# LT8316.net
KiCad netlist of a schematic drawn in Altium Designer
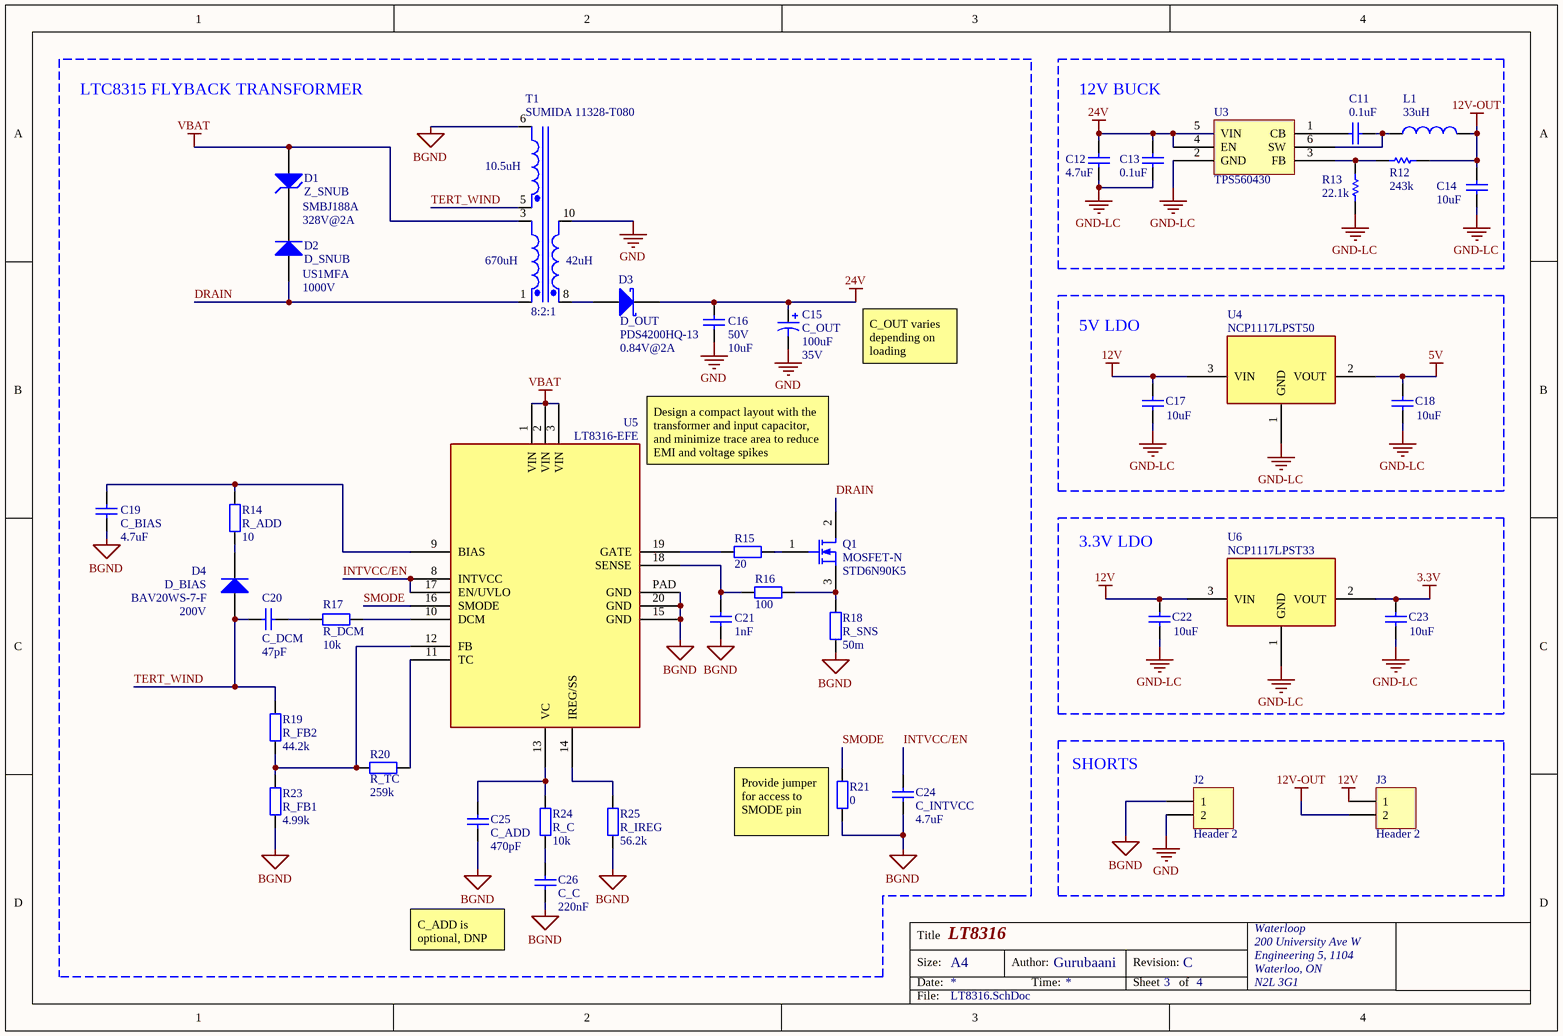
[diagram p0: LT8316.SchDoc]

(export (version "E")
  (design (tool "Eeschema 10.0.6"))
  (components
    (comp (ref "C11")
      (value "0.1uF")
      (footprint "Miscellaneous Devices:C0805")
      (description "Capacitor")
      (fields (field (name "Comment") "C_OUT") (field (name "PUBLISHER") "Altium Limited"))
      (libsource (lib "Miscellaneous Devices") (part "Cap"))
    )
    (comp (ref "C12")
      (value "4.7uF")
      (footprint "Miscellaneous Devices:C0805")
      (description "Capacitor")
      (fields (field (name "Comment") "C_OUT") (field (name "PUBLISHER") "Altium Limited"))
      (libsource (lib "Miscellaneous Devices") (part "Cap"))
    )
    (comp (ref "C13")
      (value "0.1uF")
      (footprint "Miscellaneous Devices:C0805")
      (description "Capacitor")
      (fields (field (name "Comment") "C_OUT") (field (name "PUBLISHER") "Altium Limited"))
      (libsource (lib "Miscellaneous Devices") (part "Cap"))
    )
    (comp (ref "C14")
      (value "10uF")
      (footprint "Miscellaneous Devices:C0805")
      (description "Capacitor")
      (fields (field (name "Comment") "C_OUT") (field (name "PUBLISHER") "Altium Limited"))
      (libsource (lib "Miscellaneous Devices") (part "Cap"))
    )
    (comp (ref "C15")
      (value "C_OUT")
      (footprint "RB7.6-15")
      (description "Polarized Capacitor (Radial)")
      (fields
        (field (name "ALTIUM_VALUE") "100uF")
        (field (name "VOLTAGE") "35V")
        (field (name "PUBLISHER") "Altium Limited")
      )
      (libsource (lib "Miscellaneous Devices") (part "Cap Pol1"))
    )
    (comp (ref "C16")
      (value "10uF")
      (footprint "Miscellaneous Devices:C0805")
      (description "Capacitor")
      (fields
        (field (name "VOLTAGE") "50V")
        (field (name "Comment") "C_OUT")
        (field (name "PUBLISHER") "Altium Limited")
      )
      (libsource (lib "Miscellaneous Devices") (part "Cap"))
    )
    (comp (ref "C17")
      (value "10uF")
      (footprint "Miscellaneous Devices:C0805")
      (description "Capacitor")
      (fields (field (name "Comment") "C_OUT") (field (name "PUBLISHER") "Altium Limited"))
      (libsource (lib "Miscellaneous Devices") (part "Cap"))
    )
    (comp (ref "C18")
      (value "10uF")
      (footprint "Miscellaneous Devices:C0805")
      (description "Capacitor")
      (fields (field (name "Comment") "C_OUT") (field (name "PUBLISHER") "Altium Limited"))
      (libsource (lib "Miscellaneous Devices") (part "Cap"))
    )
    (comp (ref "C19")
      (value "C_BIAS")
      (footprint "Miscellaneous Devices:C0805")
      (description "Capacitor")
      (fields (field (name "ALTIUM_VALUE") "4.7uF") (field (name "PUBLISHER") "Altium Limited"))
      (libsource (lib "Miscellaneous Devices") (part "Cap"))
    )
    (comp (ref "C20")
      (value "C_DCM")
      (footprint "Miscellaneous Devices:C0805")
      (description "Capacitor")
      (fields (field (name "ALTIUM_VALUE") "47pF") (field (name "PUBLISHER") "Altium Limited"))
      (libsource (lib "Miscellaneous Devices") (part "Cap"))
    )
    (comp (ref "C21")
      (value "1nF")
      (footprint "Miscellaneous Devices:C0805")
      (description "Capacitor")
      (fields (field (name "Comment") "C_OUT") (field (name "PUBLISHER") "Altium Limited"))
      (libsource (lib "Miscellaneous Devices") (part "Cap"))
    )
    (comp (ref "C22")
      (value "10uF")
      (footprint "Miscellaneous Devices:C0805")
      (description "Capacitor")
      (fields (field (name "Comment") "C_OUT") (field (name "PUBLISHER") "Altium Limited"))
      (libsource (lib "Miscellaneous Devices") (part "Cap"))
    )
    (comp (ref "C23")
      (value "10uF")
      (footprint "Miscellaneous Devices:C0805")
      (description "Capacitor")
      (fields (field (name "Comment") "C_OUT") (field (name "PUBLISHER") "Altium Limited"))
      (libsource (lib "Miscellaneous Devices") (part "Cap"))
    )
    (comp (ref "C24")
      (value "C_INTVCC")
      (footprint "Miscellaneous Devices:C0805")
      (description "Capacitor")
      (fields (field (name "ALTIUM_VALUE") "4.7uF") (field (name "PUBLISHER") "Altium Limited"))
      (libsource (lib "Miscellaneous Devices") (part "Cap"))
    )
    (comp (ref "C25")
      (value "C_ADD")
      (footprint "Miscellaneous Devices:C0805")
      (description "Capacitor")
      (fields (field (name "ALTIUM_VALUE") "470pF") (field (name "PUBLISHER") "Altium Limited"))
      (libsource (lib "Miscellaneous Devices") (part "Cap"))
    )
    (comp (ref "C26")
      (value "C_C")
      (footprint "Miscellaneous Devices:C0805")
      (description "Capacitor")
      (fields (field (name "ALTIUM_VALUE") "220nF") (field (name "PUBLISHER") "Altium Limited"))
      (libsource (lib "Miscellaneous Devices") (part "Cap"))
    )
    (comp (ref "D1")
      (value "Z_SNUB")
      (footprint "DO-214AA, SMB")
      (description "Zener Diode")
      (fields (field (name "REVERSE VOLTAGE") "328V@2A") (field (name "PARTNUMBER") "SMBJ188A"))
      (libsource (lib "Miscellaneous Devices") (part "D Zener"))
    )
    (comp (ref "D2")
      (value "D_SNUB")
      (footprint "SOD-123FL")
      (description "Default Diode")
      (fields (field (name "REVERSE VOLTAGE") "1000V") (field (name "PARTNUMBER") "US1MFA"))
      (libsource (lib "Miscellaneous Devices") (part "Diode"))
    )
    (comp (ref "D3")
      (value "D_OUT")
      (footprint "POWERDI5 (DPAK184P650X115-3N)")
      (description "Schottky Diode")
      (fields (field (name "FORWARD VOLTAGE") "0.84V@2A") (field (name "PARTNUMBER") "PDS4200HQ-13"))
      (libsource (lib "Miscellaneous Devices") (part "D Schottky"))
    )
    (comp (ref "D4")
      (value "D_BIAS")
      (footprint "SOD323")
      (description "Default Diode")
      (fields (field (name "REVERSE VOLTAGE") "200V") (field (name "PARTNUMBER") "BAV20WS-7-F"))
      (libsource (lib "Miscellaneous Devices") (part "Diode"))
    )
    (comp (ref "J2")
      (value "Header 2")
      (footprint "HDR1X2")
      (description "Header, 2-Pin")
      (fields (field (name "PUBLISHER") "Altium Limited"))
      (libsource (lib "Miscellaneous Connectors") (part "Header 2"))
    )
    (comp (ref "J3")
      (value "Header 2")
      (footprint "HDR1X2")
      (description "Header, 2-Pin")
      (fields (field (name "PUBLISHER") "Altium Limited"))
      (libsource (lib "Miscellaneous Connectors") (part "Header 2"))
    )
    (comp (ref "L1")
      (value "33uH")
      (footprint "INDC4532")
      (description "Inductor")
      (fields (field (name "PUBLISHER") "Altium Limited"))
      (libsource (lib "Miscellaneous Devices") (part "Inductor"))
    )
    (comp (ref "Q1")
      (value "MOSFET-N")
      (footprint "DPAK (228P972X240-3N)")
      (description "N-Channel MOSFET")
      (fields (field (name "PART NUMBER") "STD6N90K5") (field (name "PUBLISHER") "Altium Limited"))
      (libsource (lib "Miscellaneous Devices") (part "MOSFET-N"))
    )
    (comp (ref "R12")
      (value "243k")
      (footprint "Miscellaneous Devices:J1-0603")
      (description "Resistor")
      (fields (field (name "Comment") "Res1") (field (name "PUBLISHER") "Altium Limited"))
      (libsource (lib "Miscellaneous Devices") (part "Res1"))
    )
    (comp (ref "R13")
      (value "22.1k")
      (footprint "Miscellaneous Devices:J1-0603")
      (description "Resistor")
      (fields (field (name "Comment") "Res1") (field (name "PUBLISHER") "Altium Limited"))
      (libsource (lib "Miscellaneous Devices") (part "Res1"))
    )
    (comp (ref "R14")
      (value "R_ADD")
      (footprint "Miscellaneous Devices:J1-0603")
      (description "Resistor")
      (fields (field (name "ALTIUM_VALUE") "10") (field (name "PUBLISHER") "Altium Limited"))
      (libsource (lib "Miscellaneous Devices") (part "Res2"))
    )
    (comp (ref "R15")
      (value "20")
      (footprint "Miscellaneous Devices:J1-0603")
      (description "Resistor")
      (fields (field (name "Comment") "R_SNS") (field (name "PUBLISHER") "Altium Limited"))
      (libsource (lib "") (part "Res2_2"))
    )
    (comp (ref "R16")
      (value "100")
      (footprint "Miscellaneous Devices:J1-0603")
      (description "Resistor")
      (fields (field (name "Comment") "R_SNS") (field (name "PUBLISHER") "Altium Limited"))
      (libsource (lib "") (part "Res2_2"))
    )
    (comp (ref "R17")
      (value "R_DCM")
      (footprint "Miscellaneous Devices:J1-0603")
      (description "Resistor")
      (fields (field (name "ALTIUM_VALUE") "10k") (field (name "PUBLISHER") "Altium Limited"))
      (libsource (lib "") (part "Res2_1"))
    )
    (comp (ref "R18")
      (value "R_SNS")
      (footprint "Miscellaneous Devices:J1-0603")
      (description "Resistor")
      (fields (field (name "ALTIUM_VALUE") "50m") (field (name "PUBLISHER") "Altium Limited"))
      (libsource (lib "Miscellaneous Devices") (part "Res2"))
    )
    (comp (ref "R19")
      (value "R_FB2")
      (footprint "Miscellaneous Devices:J1-0603")
      (description "Resistor")
      (fields (field (name "ALTIUM_VALUE") "44.2k") (field (name "PUBLISHER") "Altium Limited"))
      (libsource (lib "") (part "Res2_3"))
    )
    (comp (ref "R20")
      (value "R_TC")
      (footprint "Miscellaneous Devices:J1-0603")
      (description "Resistor")
      (fields (field (name "ALTIUM_VALUE") "259k") (field (name "PUBLISHER") "Altium Limited"))
      (libsource (lib "") (part "Res2_1"))
    )
    (comp (ref "R21")
      (value "0")
      (footprint "Miscellaneous Devices:J1-0603")
      (description "Resistor")
      (fields (field (name "Comment") "R_C") (field (name "PUBLISHER") "Altium Limited"))
      (libsource (lib "") (part "Res2_3"))
    )
    (comp (ref "R23")
      (value "R_FB1")
      (footprint "Miscellaneous Devices:J1-0603")
      (description "Resistor")
      (fields (field (name "ALTIUM_VALUE") "4.99k") (field (name "PUBLISHER") "Altium Limited"))
      (libsource (lib "") (part "Res2_3"))
    )
    (comp (ref "R24")
      (value "R_C")
      (footprint "Miscellaneous Devices:J1-0603")
      (description "Resistor")
      (fields (field (name "ALTIUM_VALUE") "10k") (field (name "PUBLISHER") "Altium Limited"))
      (libsource (lib "") (part "Res2_3"))
    )
    (comp (ref "R25")
      (value "R_IREG")
      (footprint "Miscellaneous Devices:J1-0603")
      (description "Resistor")
      (fields (field (name "ALTIUM_VALUE") "56.2k") (field (name "PUBLISHER") "Altium Limited"))
      (libsource (lib "") (part "Res2_3"))
    )
    (comp (ref "T1")
      (value "8:2:1")
      (footprint "PQ2620")
      (description "Three-winding Transformer (Non-Ideal)")
      (fields
        (field (name "PART NUMBER") "SUMIDA 11328-T080")
        (field (name "PRIMARY INDUCTANCE") "670uH")
        (field (name "SECONDARY INDUCTANCE") "42uH")
        (field (name "TERTIARY INDUCATANCE") "10.5uH")
      )
      (libsource (lib "Miscellaneous Devices") (part "Trans3"))
    )
    (comp (ref "U3")
      (value "TPS560430")
      (footprint "SOT23-6_N")
      (description "IC REG BUCK PFM 600MA SOT23-6")
      (libsource (lib "LTC8315") (part "TPS560430"))
    )
    (comp (ref "U4")
      (value "NCP1117LPST50")
      (footprint "NCP1117LPST")
      (description "IC REG LINEAR 5V 1A SOT223")
      (libsource (lib "LTC8315") (part "NCP1117LPST50"))
    )
    (comp (ref "U5")
      (value "LT8316-EFE")
      (footprint "LTC8315/8316")
      (description "600VIN MICROPOWER, ISOLATED NO-O")
      (libsource (lib "LTC8315") (part "LT8316-EFE"))
    )
    (comp (ref "U6")
      (value "NCP1117LPST33")
      (footprint "NCP1117LPST")
      (description "IC REG LINEAR 3.3V 1A SOT223")
      (libsource (lib "LTC8315") (part "NCP1117LPST33"))
    )
  )
  (nets
    (net (code "1") (name "/DRAIN") (class "Default")
      (node (ref "D2") (pin "1") (pinfunction "A_1") (pintype "passive"))
      (node (ref "Q1") (pin "2") (pinfunction "D_2") (pintype "passive"))
      (node (ref "T1") (pin "1") (pinfunction "Sec1+_1") (pintype "passive"))
    )
    (net (code "2") (name "/INTVCC{slash}EN") (class "Default")
      (node (ref "C24") (pin "1") (pinfunction "1_1") (pintype "passive"))
      (node (ref "U5") (pin "17") (pinfunction "EN/UVLO_17") (pintype "passive"))
      (node (ref "U5") (pin "8") (pinfunction "INTVCC_8") (pintype "passive"))
    )
    (net (code "3") (name "/SMODE") (class "Default")
      (node (ref "R21") (pin "2") (pinfunction "2_2") (pintype "passive"))
      (node (ref "U5") (pin "16") (pinfunction "SMODE_16") (pintype "passive"))
    )
    (net (code "4") (name "/TERT_WIND") (class "Default")
      (node (ref "C20") (pin "1") (pinfunction "1_1") (pintype "passive"))
      (node (ref "D4") (pin "1") (pinfunction "A_1") (pintype "passive"))
      (node (ref "R19") (pin "2") (pinfunction "2_2") (pintype "passive"))
      (node (ref "T1") (pin "5") (pinfunction "Sec2+_5") (pintype "passive"))
    )
    (net (code "5") (name "3.3V") (class "Default")
      (node (ref "C23") (pin "2") (pinfunction "2_2") (pintype "passive"))
      (node (ref "U6") (pin "2") (pinfunction "VOUT_2") (pintype "passive"))
    )
    (net (code "6") (name "5V") (class "Default")
      (node (ref "C18") (pin "2") (pinfunction "2_2") (pintype "passive"))
      (node (ref "U4") (pin "2") (pinfunction "VOUT_2") (pintype "passive"))
    )
    (net (code "7") (name "12V") (class "Default")
      (node (ref "C17") (pin "2") (pinfunction "2_2") (pintype "passive"))
      (node (ref "C22") (pin "2") (pinfunction "2_2") (pintype "passive"))
      (node (ref "J3") (pin "1") (pinfunction "1_1") (pintype "passive"))
      (node (ref "U4") (pin "3") (pinfunction "VIN_3") (pintype "passive"))
      (node (ref "U6") (pin "3") (pinfunction "VIN_3") (pintype "passive"))
    )
    (net (code "8") (name "12V-OUT") (class "Default")
      (node (ref "C14") (pin "2") (pinfunction "2_2") (pintype "passive"))
      (node (ref "J3") (pin "2") (pinfunction "2_2") (pintype "passive"))
      (node (ref "L1") (pin "2") (pinfunction "2_2") (pintype "passive"))
      (node (ref "R12") (pin "1") (pinfunction "1_1") (pintype "passive"))
    )
    (net (code "9") (name "24V") (class "Default")
      (node (ref "C12") (pin "2") (pinfunction "2_2") (pintype "passive"))
      (node (ref "C13") (pin "2") (pinfunction "2_2") (pintype "passive"))
      (node (ref "C15") (pin "1") (pinfunction "1_1") (pintype "passive"))
      (node (ref "C16") (pin "2") (pinfunction "2_2") (pintype "passive"))
      (node (ref "D3") (pin "2") (pinfunction "K_2") (pintype "passive"))
      (node (ref "U3") (pin "4") (pinfunction "EN_4") (pintype "passive"))
      (node (ref "U3") (pin "5") (pinfunction "VIN_5") (pintype "passive"))
    )
    (net (code "10") (name "BGND") (class "Default")
      (node (ref "C19") (pin "1") (pinfunction "1_1") (pintype "passive"))
      (node (ref "C21") (pin "1") (pinfunction "1_1") (pintype "passive"))
      (node (ref "C24") (pin "2") (pinfunction "2_2") (pintype "passive"))
      (node (ref "C25") (pin "1") (pinfunction "1_1") (pintype "passive"))
      (node (ref "C26") (pin "1") (pinfunction "1_1") (pintype "passive"))
      (node (ref "J2") (pin "1") (pinfunction "1_1") (pintype "passive"))
      (node (ref "R18") (pin "2") (pinfunction "2_2") (pintype "passive"))
      (node (ref "R21") (pin "1") (pinfunction "1_1") (pintype "passive"))
      (node (ref "R23") (pin "1") (pinfunction "1_1") (pintype "passive"))
      (node (ref "R25") (pin "1") (pinfunction "1_1") (pintype "passive"))
      (node (ref "T1") (pin "6") (pinfunction "Sec2-_6") (pintype "passive"))
      (node (ref "U5") (pin "15") (pinfunction "GND_15") (pintype "passive"))
      (node (ref "U5") (pin "20") (pinfunction "GND_20") (pintype "passive"))
      (node (ref "U5") (pin "PAD") (pinfunction "GND_PAD") (pintype "passive"))
    )
    (net (code "11") (name "GND") (class "Default")
      (node (ref "C15") (pin "2") (pinfunction "2_2") (pintype "passive"))
      (node (ref "C16") (pin "1") (pinfunction "1_1") (pintype "passive"))
      (node (ref "J2") (pin "2") (pinfunction "2_2") (pintype "passive"))
      (node (ref "T1") (pin "10") (pinfunction "Pri-_10") (pintype "passive"))
    )
    (net (code "12") (name "GND-LC") (class "Default")
      (node (ref "C12") (pin "1") (pinfunction "1_1") (pintype "passive"))
      (node (ref "C13") (pin "1") (pinfunction "1_1") (pintype "passive"))
      (node (ref "C14") (pin "1") (pinfunction "1_1") (pintype "passive"))
      (node (ref "C17") (pin "1") (pinfunction "1_1") (pintype "passive"))
      (node (ref "C18") (pin "1") (pinfunction "1_1") (pintype "passive"))
      (node (ref "C22") (pin "1") (pinfunction "1_1") (pintype "passive"))
      (node (ref "C23") (pin "1") (pinfunction "1_1") (pintype "passive"))
      (node (ref "R13") (pin "1") (pinfunction "1_1") (pintype "passive"))
      (node (ref "U3") (pin "2") (pinfunction "GND_2") (pintype "passive"))
      (node (ref "U4") (pin "1") (pinfunction "GND_1") (pintype "passive"))
      (node (ref "U6") (pin "1") (pinfunction "GND_1") (pintype "passive"))
    )
    (net (code "13") (name "Net-(C20-Pad2)") (class "Default")
      (node (ref "C20") (pin "2") (pinfunction "2_2") (pintype "passive"))
      (node (ref "R17") (pin "2") (pinfunction "2_2") (pintype "passive"))
    )
    (net (code "14") (name "Net-(C26-Pad2)") (class "Default")
      (node (ref "C26") (pin "2") (pinfunction "2_2") (pintype "passive"))
      (node (ref "R24") (pin "1") (pinfunction "1_1") (pintype "passive"))
    )
    (net (code "15") (name "Net-(D1-K)") (class "Default")
      (node (ref "D1") (pin "2") (pinfunction "K_2") (pintype "passive"))
      (node (ref "D2") (pin "2") (pinfunction "K_2") (pintype "passive"))
    )
    (net (code "16") (name "Net-(D3-A)") (class "Default")
      (node (ref "D3") (pin "1") (pinfunction "A_1") (pintype "passive"))
      (node (ref "T1") (pin "8") (pinfunction "Pri+_8") (pintype "passive"))
    )
    (net (code "17") (name "Net-(D4-K)") (class "Default")
      (node (ref "D4") (pin "2") (pinfunction "K_2") (pintype "passive"))
      (node (ref "R14") (pin "2") (pinfunction "2_2") (pintype "passive"))
    )
    (net (code "18") (name "Net-(Q1-G)") (class "Default")
      (node (ref "Q1") (pin "1") (pinfunction "G_1") (pintype "passive"))
      (node (ref "R15") (pin "2") (pinfunction "2_2") (pintype "passive"))
    )
    (net (code "19") (name "Net-(Q1-S)") (class "Default")
      (node (ref "Q1") (pin "3") (pinfunction "S_3") (pintype "passive"))
      (node (ref "R16") (pin "2") (pinfunction "2_2") (pintype "passive"))
      (node (ref "R18") (pin "1") (pinfunction "1_1") (pintype "passive"))
    )
    (net (code "20") (name "Net-(U3-CB)") (class "Default")
      (node (ref "C11") (pin "2") (pinfunction "2_2") (pintype "passive"))
      (node (ref "U3") (pin "1") (pinfunction "CB_1") (pintype "passive"))
    )
    (net (code "21") (name "Net-(U3-FB)") (class "Default")
      (node (ref "R12") (pin "2") (pinfunction "2_2") (pintype "passive"))
      (node (ref "R13") (pin "2") (pinfunction "2_2") (pintype "passive"))
      (node (ref "U3") (pin "3") (pinfunction "FB_3") (pintype "passive"))
    )
    (net (code "22") (name "Net-(U3-SW)") (class "Default")
      (node (ref "C11") (pin "1") (pinfunction "1_1") (pintype "passive"))
      (node (ref "L1") (pin "1") (pinfunction "1_1") (pintype "passive"))
      (node (ref "U3") (pin "6") (pinfunction "SW_6") (pintype "passive"))
    )
    (net (code "23") (name "Net-(U5-BIAS)") (class "Default")
      (node (ref "C19") (pin "2") (pinfunction "2_2") (pintype "passive"))
      (node (ref "R14") (pin "1") (pinfunction "1_1") (pintype "passive"))
      (node (ref "U5") (pin "9") (pinfunction "BIAS_9") (pintype "passive"))
    )
    (net (code "24") (name "Net-(U5-DCM)") (class "Default")
      (node (ref "R17") (pin "1") (pinfunction "1_1") (pintype "passive"))
      (node (ref "U5") (pin "10") (pinfunction "DCM_10") (pintype "passive"))
    )
    (net (code "25") (name "Net-(U5-FB)") (class "Default")
      (node (ref "R19") (pin "1") (pinfunction "1_1") (pintype "passive"))
      (node (ref "R20") (pin "2") (pinfunction "2_2") (pintype "passive"))
      (node (ref "R23") (pin "2") (pinfunction "2_2") (pintype "passive"))
      (node (ref "U5") (pin "12") (pinfunction "FB_12") (pintype "passive"))
    )
    (net (code "26") (name "Net-(U5-GATE)") (class "Default")
      (node (ref "R15") (pin "1") (pinfunction "1_1") (pintype "passive"))
      (node (ref "U5") (pin "19") (pinfunction "GATE_19") (pintype "passive"))
    )
    (net (code "27") (name "Net-(U5-IREG{slash}SS)") (class "Default")
      (node (ref "R25") (pin "2") (pinfunction "2_2") (pintype "passive"))
      (node (ref "U5") (pin "14") (pinfunction "IREG/SS_14") (pintype "passive"))
    )
    (net (code "28") (name "Net-(U5-SENSE)") (class "Default")
      (node (ref "C21") (pin "2") (pinfunction "2_2") (pintype "passive"))
      (node (ref "R16") (pin "1") (pinfunction "1_1") (pintype "passive"))
      (node (ref "U5") (pin "18") (pinfunction "SENSE_18") (pintype "passive"))
    )
    (net (code "29") (name "Net-(U5-TC)") (class "Default")
      (node (ref "R20") (pin "1") (pinfunction "1_1") (pintype "passive"))
      (node (ref "U5") (pin "11") (pinfunction "TC_11") (pintype "passive"))
    )
    (net (code "30") (name "Net-(U5-VC)") (class "Default")
      (node (ref "C25") (pin "2") (pinfunction "2_2") (pintype "passive"))
      (node (ref "R24") (pin "2") (pinfunction "2_2") (pintype "passive"))
      (node (ref "U5") (pin "13") (pinfunction "VC_13") (pintype "passive"))
    )
    (net (code "31") (name "VBAT") (class "Default")
      (node (ref "D1") (pin "1") (pinfunction "A_1") (pintype "passive"))
      (node (ref "T1") (pin "3") (pinfunction "Sec1-_3") (pintype "passive"))
      (node (ref "U5") (pin "1") (pinfunction "VIN_1") (pintype "passive"))
      (node (ref "U5") (pin "2") (pinfunction "VIN_2") (pintype "passive"))
      (node (ref "U5") (pin "3") (pinfunction "VIN_3") (pintype "passive"))
    )
  )
)
